# schematic.net
KiCad netlist of a schematic drawn in Altium Designer
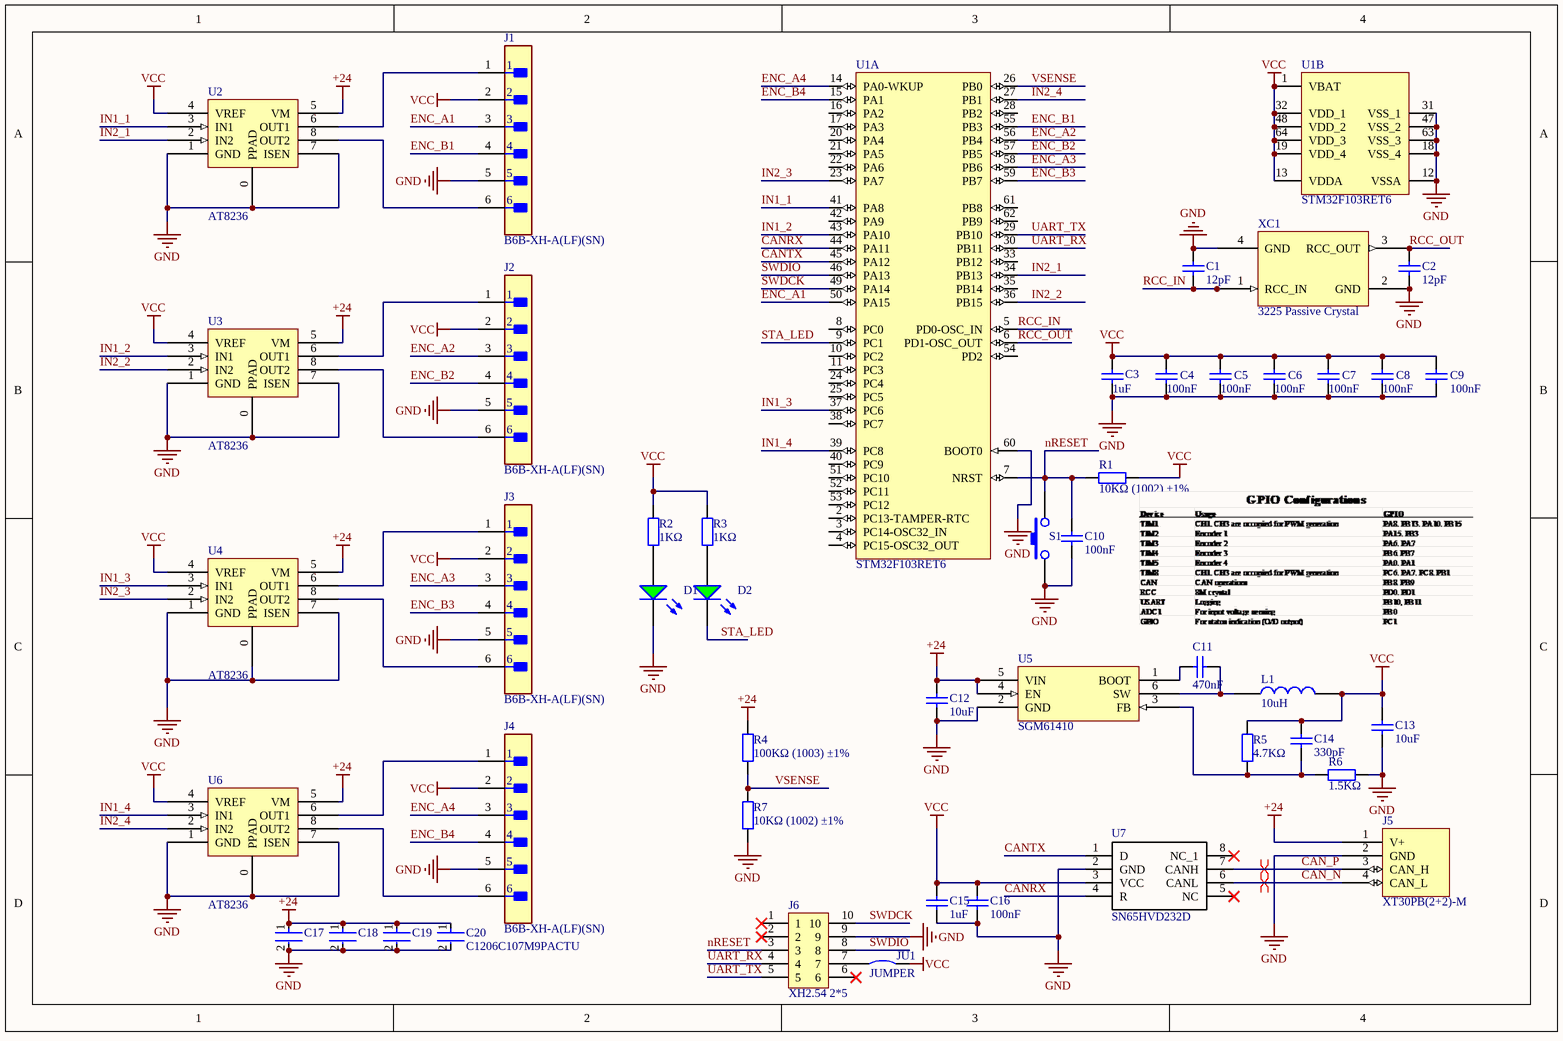
[diagram p0: schematic.SchDoc]

(export (version "E")
  (design (tool "Eeschema 10.0.6"))
  (components
    (comp (ref "C1")
      (value "12pF")
      (footprint "0603_C")
      (description "贴片电容")
      (libsource (lib "Miscellaneous Devices LC") (part "0603 12pF (120) 5% 50V"))
    )
    (comp (ref "C2")
      (value "12pF")
      (footprint "0603_C")
      (description "贴片电容")
      (libsource (lib "Miscellaneous Devices LC") (part "0603 12pF (120) 5% 50V"))
    )
    (comp (ref "C3")
      (value "1uF")
      (footprint "0603_C")
      (description "贴片电容")
      (libsource (lib "Miscellaneous Devices LC") (part "0603 1uF (105) 10% 50V"))
    )
    (comp (ref "C4")
      (value "100nF")
      (footprint "0603_C")
      (description "贴片电容")
      (libsource (lib "Miscellaneous Devices LC") (part "0603 100nF (104) 10% 50V"))
    )
    (comp (ref "C5")
      (value "100nF")
      (footprint "0603_C")
      (description "贴片电容")
      (libsource (lib "Miscellaneous Devices LC") (part "0603 100nF (104) 10% 50V"))
    )
    (comp (ref "C6")
      (value "100nF")
      (footprint "0603_C")
      (description "贴片电容")
      (libsource (lib "Miscellaneous Devices LC") (part "0603 100nF (104) 10% 50V"))
    )
    (comp (ref "C7")
      (value "100nF")
      (footprint "0603_C")
      (description "贴片电容")
      (libsource (lib "Miscellaneous Devices LC") (part "0603 100nF (104) 10% 50V"))
    )
    (comp (ref "C8")
      (value "100nF")
      (footprint "0603_C")
      (description "贴片电容")
      (libsource (lib "Miscellaneous Devices LC") (part "0603 100nF (104) 10% 50V"))
    )
    (comp (ref "C9")
      (value "100nF")
      (footprint "0603_C")
      (description "贴片电容")
      (libsource (lib "Miscellaneous Devices LC") (part "0603 100nF (104) 10% 50V"))
    )
    (comp (ref "C10")
      (value "100nF")
      (footprint "0603_C")
      (description "贴片电容")
      (libsource (lib "Miscellaneous Devices LC") (part "0603 100nF (104) 10% 50V"))
    )
    (comp (ref "C11")
      (value "470nF (474) 10% 25V")
      (footprint "0603_C")
      (description "贴片电容")
      (fields (field (name "CAPACITANCE") "470nF"))
      (libsource (lib "Miscellaneous Devices LC") (part "0603 470nF (474) 10% 25V"))
    )
    (comp (ref "C12")
      (value "10uF")
      (footprint "1206_C")
      (description "贴片电容")
      (libsource (lib "Miscellaneous Devices LC") (part "1206 10uF (106) 10% 50V"))
    )
    (comp (ref "C13")
      (value "10uF")
      (footprint "1206_C")
      (description "贴片电容")
      (libsource (lib "Miscellaneous Devices LC") (part "1206 10uF (106) 10% 50V"))
    )
    (comp (ref "C14")
      (value "330pF")
      (footprint "0603_C")
      (description "贴片电容")
      (libsource (lib "Miscellaneous Devices LC") (part "0603 330pF (331) 5% 50V"))
    )
    (comp (ref "C15")
      (value "1uF")
      (footprint "0603_C")
      (description "贴片电容")
      (libsource (lib "Miscellaneous Devices LC") (part "0603 1uF (105) 10% 50V"))
    )
    (comp (ref "C16")
      (value "100nF")
      (footprint "0603_C")
      (description "贴片电容")
      (libsource (lib "Miscellaneous Devices LC") (part "0603 100nF (104) 10% 50V"))
    )
    (comp (ref "C17")
      (value "C1206C107M9PACTU")
      (footprint "FP-C1206C-EH-MFG")
      (description "CAP CER 100UF 6.3V X5R 1206")
      (fields (field (name "TOLERANCE") "2%") (field (name "VOLTAGE") "6.3V"))
      (libsource (lib "Altium Content Vault") (part "02cd4be3c70576c341d710602a673aa"))
    )
    (comp (ref "C18")
      (value "C1206C107M9PACTU")
      (footprint "FP-C1206C-EH-MFG")
      (description "CAP CER 100UF 6.3V X5R 1206")
      (fields (field (name "TOLERANCE") "2%") (field (name "VOLTAGE") "6.3V"))
      (libsource (lib "Altium Content Vault") (part "02cd4be3c70576c341d710602a673aa"))
    )
    (comp (ref "C19")
      (value "C1206C107M9PACTU")
      (footprint "FP-C1206C-EH-MFG")
      (description "CAP CER 100UF 6.3V X5R 1206")
      (fields (field (name "TOLERANCE") "2%") (field (name "VOLTAGE") "6.3V"))
      (libsource (lib "Altium Content Vault") (part "02cd4be3c70576c341d710602a673aa"))
    )
    (comp (ref "C20")
      (value "C1206C107M9PACTU")
      (footprint "FP-C1206C-EH-MFG")
      (description "CAP CER 100UF 6.3V X5R 1206")
      (fields (field (name "TOLERANCE") "2%") (field (name "VOLTAGE") "6.3V"))
      (libsource (lib "Altium Content Vault") (part "02cd4be3c70576c341d710602a673aa"))
    )
    (comp (ref "D1")
      (value "绿灯 0603")
      (footprint "0603_LED_S1")
      (description "发光二极管")
      (libsource (lib "Miscellaneous Devices LC") (part "0603 绿灯"))
    )
    (comp (ref "D2")
      (value "绿灯 0603")
      (footprint "0603_LED_S1")
      (description "发光二极管")
      (libsource (lib "Miscellaneous Devices LC") (part "0603 绿灯"))
    )
    (comp (ref "J1")
      (value "B6B-XH-A(LF)(SN)")
      (footprint "FP-B6B-XH-A_LF_SN-MFG")
      (description "CONN HEADER VERT 6POS 2.5MM")
      (libsource (lib "Altium Content Vault") (part "f2cb566baf1c37ab5a3b8e90bbeafd6"))
    )
    (comp (ref "J2")
      (value "B6B-XH-A(LF)(SN)")
      (footprint "FP-B6B-XH-A_LF_SN-MFG")
      (description "CONN HEADER VERT 6POS 2.5MM")
      (libsource (lib "Altium Content Vault") (part "f2cb566baf1c37ab5a3b8e90bbeafd6"))
    )
    (comp (ref "J3")
      (value "B6B-XH-A(LF)(SN)")
      (footprint "FP-B6B-XH-A_LF_SN-MFG")
      (description "CONN HEADER VERT 6POS 2.5MM")
      (libsource (lib "Altium Content Vault") (part "f2cb566baf1c37ab5a3b8e90bbeafd6"))
    )
    (comp (ref "J4")
      (value "B6B-XH-A(LF)(SN)")
      (footprint "FP-B6B-XH-A_LF_SN-MFG")
      (description "CONN HEADER VERT 6POS 2.5MM")
      (libsource (lib "Altium Content Vault") (part "f2cb566baf1c37ab5a3b8e90bbeafd6"))
    )
    (comp (ref "J5")
      (value "XT30PB(2+2)-M")
      (footprint "XT30PB(2+2)-M-Footprint-1")
      (description "This is a power connector that can also be used to send/receive can signals")
      (libsource (lib "Skyli Personal Workspace") (part "XT30PB(2+2)-M"))
    )
    (comp (ref "J6")
      (value "XH2.54 2*5")
      (footprint "XH2.54-5x2")
      (libsource (lib "libadp") (part "XH2.54 2*5"))
    )
    (comp (ref "JU1")
      (value "JUMPER")
      (footprint "Jumper-2.54mm")
      (description "跳线帽")
      (libsource (lib "libadp") (part "JUMPER"))
    )
    (comp (ref "L1")
      (value "10uH")
      (footprint "IND-2520X10N")
      (description "电感")
      (libsource (lib "libadp") (part "IND"))
    )
    (comp (ref "R1")
      (value "10KΩ (1002) ±1%")
      (footprint "0603_R")
      (description "贴片电阻")
      (libsource (lib "Miscellaneous Devices LC") (part "0603 10KΩ (1002) 1%"))
    )
    (comp (ref "R2")
      (value "1KΩ")
      (footprint "0603_R")
      (description "贴片电阻")
      (libsource (lib "Miscellaneous Devices LC") (part "0603 1KΩ (1001) 1%"))
    )
    (comp (ref "R3")
      (value "1KΩ")
      (footprint "0603_R")
      (description "贴片电阻")
      (libsource (lib "Miscellaneous Devices LC") (part "0603 1KΩ (1001) 1%"))
    )
    (comp (ref "R4")
      (value "100KΩ (1003) ±1%")
      (footprint "0603_R")
      (description "贴片电阻")
      (libsource (lib "Miscellaneous Devices LC") (part "0603 100KΩ (1003) 1%"))
    )
    (comp (ref "R5")
      (value "4.7KΩ")
      (footprint "0603_R")
      (description "贴片电阻")
      (libsource (lib "Miscellaneous Devices LC") (part "0603 4.7KΩ (4701) 1%"))
    )
    (comp (ref "R6")
      (value "1.5KΩ")
      (footprint "0603_R")
      (description "贴片电阻")
      (libsource (lib "Miscellaneous Devices LC") (part "0603 1.5KΩ (1501) 1%"))
    )
    (comp (ref "R7")
      (value "10KΩ (1002) ±1%")
      (footprint "0603_R")
      (description "贴片电阻")
      (libsource (lib "") (part "0603 10KΩ (1002) 1%_1"))
    )
    (comp (ref "S1") (value "按键") (footprint "SWT3*4") (libsource (lib "libadp") (part "Button")))
    (comp (ref "U1")
      (value "STM32F103RET6")
      (footprint "STM-LQFP64_N")
      (libsource (lib "Altium Content Vault") (part "MC-ARM-STM32F103XC_D_E-SQ64"))
    )
    (comp (ref "U2")
      (value "AT8236")
      (footprint "SOP-8_EP_150mil")
      (description "Single Channel, DC, Brush motor driving IC")
      (libsource (lib "libadp") (part "AT8236"))
    )
    (comp (ref "U3")
      (value "AT8236")
      (footprint "SOP-8_EP_150mil")
      (description "Single Channel, DC, Brush motor driving IC")
      (libsource (lib "libadp") (part "AT8236"))
    )
    (comp (ref "U4")
      (value "AT8236")
      (footprint "SOP-8_EP_150mil")
      (description "Single Channel, DC, Brush motor driving IC")
      (libsource (lib "libadp") (part "AT8236"))
    )
    (comp (ref "U5")
      (value "SGM61410")
      (footprint "SOT23-6")
      (description "1.2MHz, 600mA, 42V Synchronous Buck Converter")
      (libsource (lib "libadp") (part "SGM61410XN6G"))
    )
    (comp (ref "U6")
      (value "AT8236")
      (footprint "SOP-8_EP_150mil")
      (description "Single Channel, DC, Brush motor driving IC")
      (libsource (lib "libadp") (part "AT8236"))
    )
    (comp (ref "U7")
      (value "SN65HVD232D")
      (footprint "SOIC127P600X175-8N")
      (description "3.3-V CAN TRANSCEIVER")
      (fields (field (name "MOUSER PART NUMBER") "595-SN65HVD232D") (field (name "RS PART NUMBER") "1977506"))
      (libsource (lib "libadp") (part "SN65HVD232D"))
    )
    (comp (ref "XC1")
      (value "3225 Passive Crystal")
      (footprint "SMD-3225")
      (libsource (lib "libadp") (part "3225 Passive Crystal"))
    )
  )
  (nets
    (net (code "1") (name "+24") (class "Default")
      (node (ref "C12") (pin "2") (pinfunction "2_2") (pintype "passive"))
      (node (ref "C17") (pin "1") (pinfunction "1_1") (pintype "passive"))
      (node (ref "C18") (pin "1") (pinfunction "1_1") (pintype "passive"))
      (node (ref "C19") (pin "1") (pinfunction "1_1") (pintype "passive"))
      (node (ref "C20") (pin "1") (pinfunction "1_1") (pintype "passive"))
      (node (ref "J5") (pin "1") (pinfunction "V+_1") (pintype "power_in"))
      (node (ref "R4") (pin "2") (pinfunction "2_2") (pintype "passive"))
      (node (ref "U2") (pin "5") (pinfunction "VM_5") (pintype "power_in"))
      (node (ref "U3") (pin "5") (pinfunction "VM_5") (pintype "power_in"))
      (node (ref "U4") (pin "5") (pinfunction "VM_5") (pintype "power_in"))
      (node (ref "U5") (pin "4") (pinfunction "EN_4") (pintype "input"))
      (node (ref "U5") (pin "5") (pinfunction "VIN_5") (pintype "power_in"))
      (node (ref "U6") (pin "5") (pinfunction "VM_5") (pintype "power_in"))
    )
    (net (code "2") (name "/CANRX") (class "Default")
      (node (ref "U1") (pin "44") (pinfunction "PA11_44") (pintype "bidirectional"))
      (node (ref "U7") (pin "4") (pinfunction "R_4") (pintype "passive"))
    )
    (net (code "3") (name "/CANTX") (class "Default")
      (node (ref "U1") (pin "45") (pinfunction "PA12_45") (pintype "bidirectional"))
      (node (ref "U7") (pin "1") (pinfunction "D_1") (pintype "passive"))
    )
    (net (code "4") (name "/CAN_N") (class "Default")
      (node (ref "J5") (pin "4") (pinfunction "CAN_L_4") (pintype "bidirectional"))
      (node (ref "U7") (pin "6") (pinfunction "CANL_6") (pintype "passive"))
    )
    (net (code "5") (name "/CAN_P") (class "Default")
      (node (ref "J5") (pin "3") (pinfunction "CAN_H_3") (pintype "bidirectional"))
      (node (ref "U7") (pin "7") (pinfunction "CANH_7") (pintype "passive"))
    )
    (net (code "6") (name "/ENC_A1") (class "Default")
      (node (ref "J1") (pin "3") (pinfunction "3_3") (pintype "passive"))
      (node (ref "U1") (pin "50") (pinfunction "PA15_50") (pintype "bidirectional"))
    )
    (net (code "7") (name "/ENC_A2") (class "Default")
      (node (ref "J2") (pin "3") (pinfunction "3_3") (pintype "passive"))
      (node (ref "U1") (pin "56") (pinfunction "PB4_56") (pintype "bidirectional"))
    )
    (net (code "8") (name "/ENC_A3") (class "Default")
      (node (ref "J3") (pin "3") (pinfunction "3_3") (pintype "passive"))
      (node (ref "U1") (pin "58") (pinfunction "PB6_58") (pintype "bidirectional"))
    )
    (net (code "9") (name "/ENC_A4") (class "Default")
      (node (ref "J4") (pin "3") (pinfunction "3_3") (pintype "passive"))
      (node (ref "U1") (pin "14") (pinfunction "PA0-WKUP_14") (pintype "bidirectional"))
    )
    (net (code "10") (name "/ENC_B1") (class "Default")
      (node (ref "J1") (pin "4") (pinfunction "4_4") (pintype "passive"))
      (node (ref "U1") (pin "55") (pinfunction "PB3_55") (pintype "bidirectional"))
    )
    (net (code "11") (name "/ENC_B2") (class "Default")
      (node (ref "J2") (pin "4") (pinfunction "4_4") (pintype "passive"))
      (node (ref "U1") (pin "57") (pinfunction "PB5_57") (pintype "bidirectional"))
    )
    (net (code "12") (name "/ENC_B3") (class "Default")
      (node (ref "J3") (pin "4") (pinfunction "4_4") (pintype "passive"))
      (node (ref "U1") (pin "59") (pinfunction "PB7_59") (pintype "bidirectional"))
    )
    (net (code "13") (name "/ENC_B4") (class "Default")
      (node (ref "J4") (pin "4") (pinfunction "4_4") (pintype "passive"))
      (node (ref "U1") (pin "15") (pinfunction "PA1_15") (pintype "bidirectional"))
    )
    (net (code "14") (name "/IN1_1") (class "Default")
      (node (ref "U1") (pin "41") (pinfunction "PA8_41") (pintype "bidirectional"))
      (node (ref "U2") (pin "3") (pinfunction "IN1_3") (pintype "input"))
    )
    (net (code "15") (name "/IN1_2") (class "Default")
      (node (ref "U1") (pin "43") (pinfunction "PA10_43") (pintype "bidirectional"))
      (node (ref "U3") (pin "3") (pinfunction "IN1_3") (pintype "input"))
    )
    (net (code "16") (name "/IN1_3") (class "Default")
      (node (ref "U1") (pin "37") (pinfunction "PC6_37") (pintype "bidirectional"))
      (node (ref "U4") (pin "3") (pinfunction "IN1_3") (pintype "input"))
    )
    (net (code "17") (name "/IN1_4") (class "Default")
      (node (ref "U1") (pin "39") (pinfunction "PC8_39") (pintype "bidirectional"))
      (node (ref "U6") (pin "3") (pinfunction "IN1_3") (pintype "input"))
    )
    (net (code "18") (name "/IN2_1") (class "Default")
      (node (ref "U1") (pin "34") (pinfunction "PB13_34") (pintype "bidirectional"))
      (node (ref "U2") (pin "2") (pinfunction "IN2_2") (pintype "input"))
    )
    (net (code "19") (name "/IN2_2") (class "Default")
      (node (ref "U1") (pin "36") (pinfunction "PB15_36") (pintype "bidirectional"))
      (node (ref "U3") (pin "2") (pinfunction "IN2_2") (pintype "input"))
    )
    (net (code "20") (name "/IN2_3") (class "Default")
      (node (ref "U1") (pin "23") (pinfunction "PA7_23") (pintype "bidirectional"))
      (node (ref "U4") (pin "2") (pinfunction "IN2_2") (pintype "input"))
    )
    (net (code "21") (name "/IN2_4") (class "Default")
      (node (ref "U1") (pin "27") (pinfunction "PB1_27") (pintype "bidirectional"))
      (node (ref "U6") (pin "2") (pinfunction "IN2_2") (pintype "input"))
    )
    (net (code "22") (name "/RCC_IN") (class "Default")
      (node (ref "C1") (pin "1") (pinfunction "1_1") (pintype "passive"))
      (node (ref "U1") (pin "5") (pinfunction "PD0-OSC_IN_5") (pintype "bidirectional"))
      (node (ref "XC1") (pin "1") (pinfunction "RCC_IN_1") (pintype "input"))
    )
    (net (code "23") (name "/RCC_OUT") (class "Default")
      (node (ref "C2") (pin "2") (pinfunction "2_2") (pintype "passive"))
      (node (ref "U1") (pin "6") (pinfunction "PD1-OSC_OUT_6") (pintype "bidirectional"))
      (node (ref "XC1") (pin "3") (pinfunction "RCC_OUT_3") (pintype "output"))
    )
    (net (code "24") (name "/STA_LED") (class "Default")
      (node (ref "D2") (pin "K") (pinfunction "K_K") (pintype "passive"))
      (node (ref "U1") (pin "9") (pinfunction "PC1_9") (pintype "bidirectional"))
    )
    (net (code "25") (name "/SWDCK") (class "Default")
      (node (ref "J6") (pin "10") (pinfunction "10_10") (pintype "passive"))
      (node (ref "U1") (pin "49") (pinfunction "PA14_49") (pintype "bidirectional"))
    )
    (net (code "26") (name "/SWDIO") (class "Default")
      (node (ref "J6") (pin "8") (pinfunction "8_8") (pintype "passive"))
      (node (ref "U1") (pin "46") (pinfunction "PA13_46") (pintype "bidirectional"))
    )
    (net (code "27") (name "/UART_RX") (class "Default")
      (node (ref "J6") (pin "4") (pinfunction "4_4") (pintype "passive"))
      (node (ref "U1") (pin "30") (pinfunction "PB11_30") (pintype "bidirectional"))
    )
    (net (code "28") (name "/UART_TX") (class "Default")
      (node (ref "J6") (pin "5") (pinfunction "5_5") (pintype "passive"))
      (node (ref "U1") (pin "29") (pinfunction "PB10_29") (pintype "bidirectional"))
    )
    (net (code "29") (name "/VSENSE") (class "Default")
      (node (ref "R4") (pin "1") (pinfunction "1_1") (pintype "passive"))
      (node (ref "R7") (pin "2") (pinfunction "2_2") (pintype "passive"))
      (node (ref "U1") (pin "26") (pinfunction "PB0_26") (pintype "bidirectional"))
    )
    (net (code "30") (name "/nRESET") (class "Default")
      (node (ref "C10") (pin "2") (pinfunction "2_2") (pintype "passive"))
      (node (ref "J6") (pin "3") (pinfunction "3_3") (pintype "passive"))
      (node (ref "R1") (pin "1") (pinfunction "1_1") (pintype "passive"))
      (node (ref "S1") (pin "2") (pinfunction "2_2") (pintype "passive"))
      (node (ref "U1") (pin "7") (pinfunction "NRST_7") (pintype "bidirectional"))
    )
    (net (code "31") (name "GND") (class "Default")
      (node (ref "C1") (pin "2") (pinfunction "2_2") (pintype "passive"))
      (node (ref "C10") (pin "1") (pinfunction "1_1") (pintype "passive"))
      (node (ref "C12") (pin "1") (pinfunction "1_1") (pintype "passive"))
      (node (ref "C13") (pin "1") (pinfunction "1_1") (pintype "passive"))
      (node (ref "C15") (pin "1") (pinfunction "1_1") (pintype "passive"))
      (node (ref "C16") (pin "1") (pinfunction "1_1") (pintype "passive"))
      (node (ref "C17") (pin "2") (pinfunction "2_2") (pintype "passive"))
      (node (ref "C18") (pin "2") (pinfunction "2_2") (pintype "passive"))
      (node (ref "C19") (pin "2") (pinfunction "2_2") (pintype "passive"))
      (node (ref "C2") (pin "1") (pinfunction "1_1") (pintype "passive"))
      (node (ref "C20") (pin "2") (pinfunction "2_2") (pintype "passive"))
      (node (ref "C3") (pin "1") (pinfunction "1_1") (pintype "passive"))
      (node (ref "C4") (pin "1") (pinfunction "1_1") (pintype "passive"))
      (node (ref "C5") (pin "1") (pinfunction "1_1") (pintype "passive"))
      (node (ref "C6") (pin "1") (pinfunction "1_1") (pintype "passive"))
      (node (ref "C7") (pin "1") (pinfunction "1_1") (pintype "passive"))
      (node (ref "C8") (pin "1") (pinfunction "1_1") (pintype "passive"))
      (node (ref "C9") (pin "1") (pinfunction "1_1") (pintype "passive"))
      (node (ref "D1") (pin "K") (pinfunction "K_K") (pintype "passive"))
      (node (ref "J1") (pin "5") (pinfunction "5_5") (pintype "passive"))
      (node (ref "J2") (pin "5") (pinfunction "5_5") (pintype "passive"))
      (node (ref "J3") (pin "5") (pinfunction "5_5") (pintype "passive"))
      (node (ref "J4") (pin "5") (pinfunction "5_5") (pintype "passive"))
      (node (ref "J5") (pin "2") (pinfunction "GND_2") (pintype "power_in"))
      (node (ref "J6") (pin "9") (pinfunction "9_9") (pintype "passive"))
      (node (ref "R6") (pin "1") (pinfunction "1_1") (pintype "passive"))
      (node (ref "R7") (pin "1") (pinfunction "1_1") (pintype "passive"))
      (node (ref "S1") (pin "1") (pinfunction "1_1") (pintype "passive"))
      (node (ref "U1") (pin "12") (pinfunction "VSSA_12") (pintype "power_in"))
      (node (ref "U1") (pin "18") (pinfunction "VSS_4_18") (pintype "power_in"))
      (node (ref "U1") (pin "31") (pinfunction "VSS_1_31") (pintype "power_in"))
      (node (ref "U1") (pin "47") (pinfunction "VSS_2_47") (pintype "power_in"))
      (node (ref "U1") (pin "60") (pinfunction "BOOT0_60") (pintype "input"))
      (node (ref "U1") (pin "63") (pinfunction "VSS_3_63") (pintype "power_in"))
      (node (ref "U2") (pin "0") (pinfunction "PPAD_0") (pintype "power_in"))
      (node (ref "U2") (pin "1") (pinfunction "GND_1") (pintype "power_in"))
      (node (ref "U2") (pin "7") (pinfunction "ISEN_7") (pintype "passive"))
      (node (ref "U3") (pin "0") (pinfunction "PPAD_0") (pintype "power_in"))
      (node (ref "U3") (pin "1") (pinfunction "GND_1") (pintype "power_in"))
      (node (ref "U3") (pin "7") (pinfunction "ISEN_7") (pintype "passive"))
      (node (ref "U4") (pin "0") (pinfunction "PPAD_0") (pintype "power_in"))
      (node (ref "U4") (pin "1") (pinfunction "GND_1") (pintype "power_in"))
      (node (ref "U4") (pin "7") (pinfunction "ISEN_7") (pintype "passive"))
      (node (ref "U5") (pin "2") (pinfunction "GND_2") (pintype "power_in"))
      (node (ref "U6") (pin "0") (pinfunction "PPAD_0") (pintype "power_in"))
      (node (ref "U6") (pin "1") (pinfunction "GND_1") (pintype "power_in"))
      (node (ref "U6") (pin "7") (pinfunction "ISEN_7") (pintype "passive"))
      (node (ref "U7") (pin "2") (pinfunction "GND_2") (pintype "power_in"))
      (node (ref "XC1") (pin "2") (pinfunction "GND_2") (pintype "power_in"))
      (node (ref "XC1") (pin "4") (pinfunction "GND_4") (pintype "power_in"))
    )
    (net (code "32") (name "Net-(D1-PadA)") (class "Default")
      (node (ref "D1") (pin "A") (pinfunction "A_A") (pintype "passive"))
      (node (ref "R2") (pin "1") (pinfunction "1_1") (pintype "passive"))
    )
    (net (code "33") (name "Net-(D2-PadA)") (class "Default")
      (node (ref "D2") (pin "A") (pinfunction "A_A") (pintype "passive"))
      (node (ref "R3") (pin "1") (pinfunction "1_1") (pintype "passive"))
    )
    (net (code "34") (name "Net-(J6-Pad7)") (class "Default")
      (node (ref "J6") (pin "7") (pinfunction "7_7") (pintype "passive"))
      (node (ref "JU1") (pin "1") (pinfunction "1_1") (pintype "passive"))
    )
    (net (code "35") (name "Net-(U2-OUT1)") (class "Default")
      (node (ref "J1") (pin "1") (pinfunction "1_1") (pintype "passive"))
      (node (ref "U2") (pin "6") (pinfunction "OUT1_6") (pintype "power_in"))
    )
    (net (code "36") (name "Net-(U2-OUT2)") (class "Default")
      (node (ref "J1") (pin "6") (pinfunction "6_6") (pintype "passive"))
      (node (ref "U2") (pin "8") (pinfunction "OUT2_8") (pintype "power_in"))
    )
    (net (code "37") (name "Net-(U3-OUT1)") (class "Default")
      (node (ref "J2") (pin "1") (pinfunction "1_1") (pintype "passive"))
      (node (ref "U3") (pin "6") (pinfunction "OUT1_6") (pintype "power_in"))
    )
    (net (code "38") (name "Net-(U3-OUT2)") (class "Default")
      (node (ref "J2") (pin "6") (pinfunction "6_6") (pintype "passive"))
      (node (ref "U3") (pin "8") (pinfunction "OUT2_8") (pintype "power_in"))
    )
    (net (code "39") (name "Net-(U4-OUT1)") (class "Default")
      (node (ref "J3") (pin "1") (pinfunction "1_1") (pintype "passive"))
      (node (ref "U4") (pin "6") (pinfunction "OUT1_6") (pintype "power_in"))
    )
    (net (code "40") (name "Net-(U4-OUT2)") (class "Default")
      (node (ref "J3") (pin "6") (pinfunction "6_6") (pintype "passive"))
      (node (ref "U4") (pin "8") (pinfunction "OUT2_8") (pintype "power_in"))
    )
    (net (code "41") (name "Net-(U5-BOOT)") (class "Default")
      (node (ref "C11") (pin "2") (pinfunction "2_2") (pintype "passive"))
      (node (ref "U5") (pin "1") (pinfunction "BOOT_1") (pintype "power_in"))
    )
    (net (code "42") (name "Net-(U5-FB)") (class "Default")
      (node (ref "C14") (pin "1") (pinfunction "1_1") (pintype "passive"))
      (node (ref "R5") (pin "1") (pinfunction "1_1") (pintype "passive"))
      (node (ref "R6") (pin "2") (pinfunction "2_2") (pintype "passive"))
      (node (ref "U5") (pin "3") (pinfunction "FB_3") (pintype "input"))
    )
    (net (code "43") (name "Net-(U5-SW)") (class "Default")
      (node (ref "C11") (pin "1") (pinfunction "1_1") (pintype "passive"))
      (node (ref "L1") (pin "1") (pinfunction "1_1") (pintype "passive"))
      (node (ref "U5") (pin "6") (pinfunction "SW_6") (pintype "power_in"))
    )
    (net (code "44") (name "Net-(U6-OUT1)") (class "Default")
      (node (ref "J4") (pin "1") (pinfunction "1_1") (pintype "passive"))
      (node (ref "U6") (pin "6") (pinfunction "OUT1_6") (pintype "power_in"))
    )
    (net (code "45") (name "Net-(U6-OUT2)") (class "Default")
      (node (ref "J4") (pin "6") (pinfunction "6_6") (pintype "passive"))
      (node (ref "U6") (pin "8") (pinfunction "OUT2_8") (pintype "power_in"))
    )
    (net (code "46") (name "VCC") (class "Default")
      (node (ref "C13") (pin "2") (pinfunction "2_2") (pintype "passive"))
      (node (ref "C14") (pin "2") (pinfunction "2_2") (pintype "passive"))
      (node (ref "C15") (pin "2") (pinfunction "2_2") (pintype "passive"))
      (node (ref "C16") (pin "2") (pinfunction "2_2") (pintype "passive"))
      (node (ref "C3") (pin "2") (pinfunction "2_2") (pintype "passive"))
      (node (ref "C4") (pin "2") (pinfunction "2_2") (pintype "passive"))
      (node (ref "C5") (pin "2") (pinfunction "2_2") (pintype "passive"))
      (node (ref "C6") (pin "2") (pinfunction "2_2") (pintype "passive"))
      (node (ref "C7") (pin "2") (pinfunction "2_2") (pintype "passive"))
      (node (ref "C8") (pin "2") (pinfunction "2_2") (pintype "passive"))
      (node (ref "C9") (pin "2") (pinfunction "2_2") (pintype "passive"))
      (node (ref "J1") (pin "2") (pinfunction "2_2") (pintype "passive"))
      (node (ref "J2") (pin "2") (pinfunction "2_2") (pintype "passive"))
      (node (ref "J3") (pin "2") (pinfunction "2_2") (pintype "passive"))
      (node (ref "J4") (pin "2") (pinfunction "2_2") (pintype "passive"))
      (node (ref "JU1") (pin "2") (pintype "passive"))
      (node (ref "L1") (pin "2") (pinfunction "2_2") (pintype "passive"))
      (node (ref "R1") (pin "2") (pinfunction "2_2") (pintype "passive"))
      (node (ref "R2") (pin "2") (pinfunction "2_2") (pintype "passive"))
      (node (ref "R3") (pin "2") (pinfunction "2_2") (pintype "passive"))
      (node (ref "R5") (pin "2") (pinfunction "2_2") (pintype "passive"))
      (node (ref "U1") (pin "1") (pinfunction "VBAT_1") (pintype "power_in"))
      (node (ref "U1") (pin "13") (pinfunction "VDDA_13") (pintype "power_in"))
      (node (ref "U1") (pin "19") (pinfunction "VDD_4_19") (pintype "power_in"))
      (node (ref "U1") (pin "32") (pinfunction "VDD_1_32") (pintype "power_in"))
      (node (ref "U1") (pin "48") (pinfunction "VDD_2_48") (pintype "power_in"))
      (node (ref "U1") (pin "64") (pinfunction "VDD_3_64") (pintype "power_in"))
      (node (ref "U2") (pin "4") (pinfunction "VREF_4") (pintype "power_in"))
      (node (ref "U3") (pin "4") (pinfunction "VREF_4") (pintype "power_in"))
      (node (ref "U4") (pin "4") (pinfunction "VREF_4") (pintype "power_in"))
      (node (ref "U6") (pin "4") (pinfunction "VREF_4") (pintype "power_in"))
      (node (ref "U7") (pin "3") (pinfunction "VCC_3") (pintype "power_in"))
    )
    (net (code "47") (name "unconnected-(J6-Pad1)") (class "Default")
      (node (ref "J6") (pin "1") (pinfunction "1_1") (pintype "passive+no_connect"))
    )
    (net (code "48") (name "unconnected-(J6-Pad2)") (class "Default")
      (node (ref "J6") (pin "2") (pinfunction "2_2") (pintype "passive+no_connect"))
    )
    (net (code "49") (name "unconnected-(J6-Pad6)") (class "Default")
      (node (ref "J6") (pin "6") (pinfunction "6_6") (pintype "passive+no_connect"))
    )
    (net (code "50") (name "unconnected-(U1A-PA2-Pad16)") (class "Default")
      (node (ref "U1") (pin "16") (pinfunction "PA2_16") (pintype "bidirectional"))
    )
    (net (code "51") (name "unconnected-(U1A-PA3-Pad17)") (class "Default")
      (node (ref "U1") (pin "17") (pinfunction "PA3_17") (pintype "bidirectional"))
    )
    (net (code "52") (name "unconnected-(U1A-PA4-Pad20)") (class "Default")
      (node (ref "U1") (pin "20") (pinfunction "PA4_20") (pintype "bidirectional"))
    )
    (net (code "53") (name "unconnected-(U1A-PA5-Pad21)") (class "Default")
      (node (ref "U1") (pin "21") (pinfunction "PA5_21") (pintype "bidirectional"))
    )
    (net (code "54") (name "unconnected-(U1A-PA6-Pad22)") (class "Default")
      (node (ref "U1") (pin "22") (pinfunction "PA6_22") (pintype "bidirectional"))
    )
    (net (code "55") (name "unconnected-(U1A-PA9-Pad42)") (class "Default")
      (node (ref "U1") (pin "42") (pinfunction "PA9_42") (pintype "bidirectional"))
    )
    (net (code "56") (name "unconnected-(U1A-PB2-Pad28)") (class "Default")
      (node (ref "U1") (pin "28") (pinfunction "PB2_28") (pintype "bidirectional"))
    )
    (net (code "57") (name "unconnected-(U1A-PB8-Pad61)") (class "Default")
      (node (ref "U1") (pin "61") (pinfunction "PB8_61") (pintype "bidirectional"))
    )
    (net (code "58") (name "unconnected-(U1A-PB9-Pad62)") (class "Default")
      (node (ref "U1") (pin "62") (pinfunction "PB9_62") (pintype "bidirectional"))
    )
    (net (code "59") (name "unconnected-(U1A-PB12-Pad33)") (class "Default")
      (node (ref "U1") (pin "33") (pinfunction "PB12_33") (pintype "bidirectional"))
    )
    (net (code "60") (name "unconnected-(U1A-PB14-Pad35)") (class "Default")
      (node (ref "U1") (pin "35") (pinfunction "PB14_35") (pintype "bidirectional"))
    )
    (net (code "61") (name "unconnected-(U1A-PC0-Pad8)") (class "Default")
      (node (ref "U1") (pin "8") (pinfunction "PC0_8") (pintype "bidirectional"))
    )
    (net (code "62") (name "unconnected-(U1A-PC2-Pad10)") (class "Default")
      (node (ref "U1") (pin "10") (pinfunction "PC2_10") (pintype "bidirectional"))
    )
    (net (code "63") (name "unconnected-(U1A-PC3-Pad11)") (class "Default")
      (node (ref "U1") (pin "11") (pinfunction "PC3_11") (pintype "bidirectional"))
    )
    (net (code "64") (name "unconnected-(U1A-PC4-Pad24)") (class "Default")
      (node (ref "U1") (pin "24") (pinfunction "PC4_24") (pintype "bidirectional"))
    )
    (net (code "65") (name "unconnected-(U1A-PC5-Pad25)") (class "Default")
      (node (ref "U1") (pin "25") (pinfunction "PC5_25") (pintype "bidirectional"))
    )
    (net (code "66") (name "unconnected-(U1A-PC7-Pad38)") (class "Default")
      (node (ref "U1") (pin "38") (pinfunction "PC7_38") (pintype "bidirectional"))
    )
    (net (code "67") (name "unconnected-(U1A-PC9-Pad40)") (class "Default")
      (node (ref "U1") (pin "40") (pinfunction "PC9_40") (pintype "bidirectional"))
    )
    (net (code "68") (name "unconnected-(U1A-PC10-Pad51)") (class "Default")
      (node (ref "U1") (pin "51") (pinfunction "PC10_51") (pintype "bidirectional"))
    )
    (net (code "69") (name "unconnected-(U1A-PC11-Pad52)") (class "Default")
      (node (ref "U1") (pin "52") (pinfunction "PC11_52") (pintype "bidirectional"))
    )
    (net (code "70") (name "unconnected-(U1A-PC12-Pad53)") (class "Default")
      (node (ref "U1") (pin "53") (pinfunction "PC12_53") (pintype "bidirectional"))
    )
    (net (code "71") (name "unconnected-(U1A-PC13-TAMPER-RTC-Pad2)") (class "Default")
      (node (ref "U1") (pin "2") (pinfunction "PC13-TAMPER-RTC_2") (pintype "bidirectional"))
    )
    (net (code "72") (name "unconnected-(U1A-PC14-OSC32_IN-Pad3)") (class "Default")
      (node (ref "U1") (pin "3") (pinfunction "PC14-OSC32_IN_3") (pintype "bidirectional"))
    )
    (net (code "73") (name "unconnected-(U1A-PC15-OSC32_OUT-Pad4)") (class "Default")
      (node (ref "U1") (pin "4") (pinfunction "PC15-OSC32_OUT_4") (pintype "bidirectional"))
    )
    (net (code "74") (name "unconnected-(U1A-PD2-Pad54)") (class "Default")
      (node (ref "U1") (pin "54") (pinfunction "PD2_54") (pintype "bidirectional"))
    )
    (net (code "75") (name "unconnected-(U7-NC-Pad5)") (class "Default")
      (node (ref "U7") (pin "5") (pinfunction "NC_5") (pintype "passive+no_connect"))
    )
    (net (code "76") (name "unconnected-(U7-NC_1-Pad8)") (class "Default")
      (node (ref "U7") (pin "8") (pinfunction "NC_1_8") (pintype "passive+no_connect"))
    )
  )
)
